# DRAM_DDR4_bank_1_Connector.net
KiCad netlist of a schematic drawn in Altium Designer
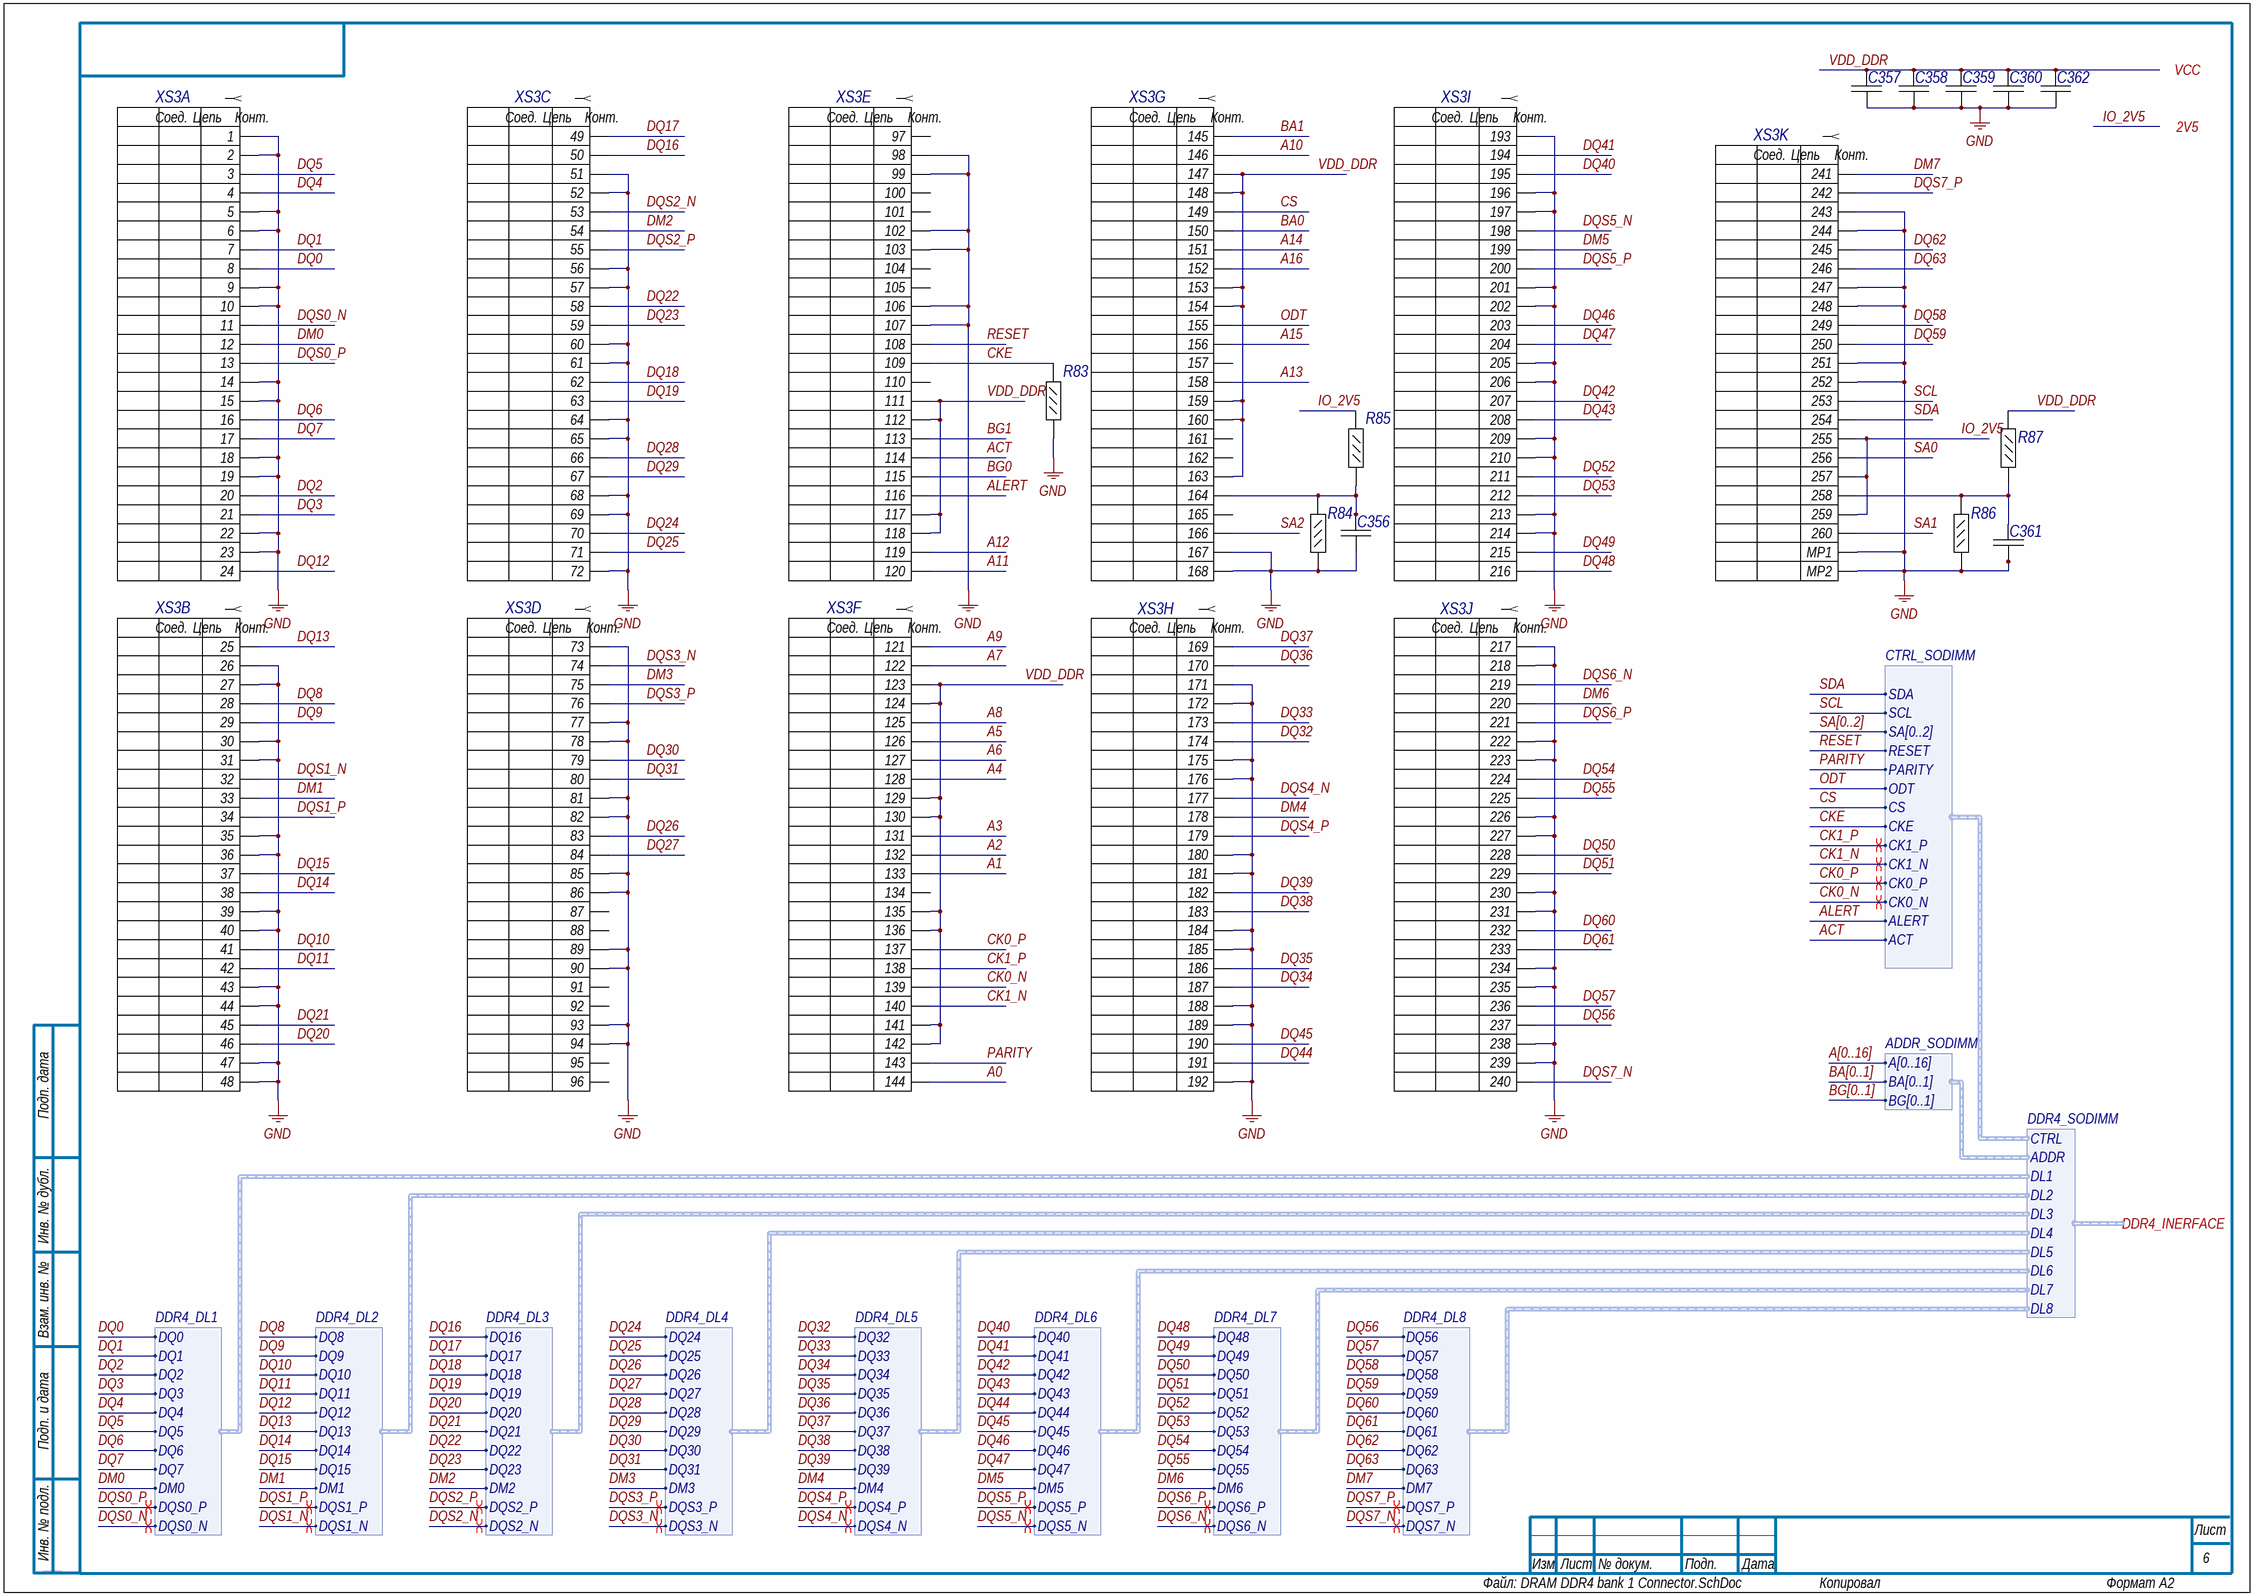
[diagram p0: DRAM DDR4 bank 1 Connector.SchDoc]

(export (version "E")
  (design (tool "Eeschema 10.0.6"))
  (components
    (comp (ref "C356")
      (value "C1005X7R1E104M")
      (footprint "CAPC1005X55X10LL05")
      (description "Chip Capacitor, 0.1 uF, +/- 20%, 25 V, -55 to 125 degC, 0402 (1005 Metric), RoHS, Tape and Reel")
      (fields (field (name "TOLERANCE") "20%"))
      (libsource (lib "MiniPC DB") (part "CAP_NP"))
    )
    (comp (ref "C357")
      (value "C1005X7R1E104M")
      (footprint "CAPC1005X55X10LL05")
      (description "Chip Capacitor, 0.1 uF, +/- 20%, 25 V, -55 to 125 degC, 0402 (1005 Metric), RoHS, Tape and Reel")
      (fields (field (name "TOLERANCE") "20%"))
      (libsource (lib "MiniPC DB") (part "CAP_NP"))
    )
    (comp (ref "C358")
      (value "C1005X7R1E104M")
      (footprint "CAPC1005X55X10LL05")
      (description "Chip Capacitor, 0.1 uF, +/- 20%, 25 V, -55 to 125 degC, 0402 (1005 Metric), RoHS, Tape and Reel")
      (fields (field (name "TOLERANCE") "20%"))
      (libsource (lib "MiniPC DB") (part "CAP_NP"))
    )
    (comp (ref "C359")
      (value "C1005X7R1E104M")
      (footprint "CAPC1005X55X10LL05")
      (description "Chip Capacitor, 0.1 uF, +/- 20%, 25 V, -55 to 125 degC, 0402 (1005 Metric), RoHS, Tape and Reel")
      (fields (field (name "TOLERANCE") "20%"))
      (libsource (lib "MiniPC DB") (part "CAP_NP"))
    )
    (comp (ref "C360")
      (value "C1005X7R1E104M")
      (footprint "CAPC1005X55X10LL05")
      (description "Chip Capacitor, 0.1 uF, +/- 20%, 25 V, -55 to 125 degC, 0402 (1005 Metric), RoHS, Tape and Reel")
      (fields (field (name "TOLERANCE") "20%"))
      (libsource (lib "MiniPC DB") (part "CAP_NP"))
    )
    (comp (ref "C361")
      (value "C1005X7R1E104M")
      (footprint "CAPC1005X55X10LL05")
      (description "Chip Capacitor, 0.1 uF, +/- 20%, 25 V, -55 to 125 degC, 0402 (1005 Metric), RoHS, Tape and Reel")
      (fields (field (name "TOLERANCE") "20%"))
      (libsource (lib "MiniPC DB") (part "CAP_NP"))
    )
    (comp (ref "C362")
      (value "C1005X7R1E104M")
      (footprint "CAPC1005X55X10LL05")
      (description "Chip Capacitor, 0.1 uF, +/- 20%, 25 V, -55 to 125 degC, 0402 (1005 Metric), RoHS, Tape and Reel")
      (fields (field (name "TOLERANCE") "20%"))
      (libsource (lib "MiniPC DB") (part "CAP_NP"))
    )
    (comp (ref "R83")
      (value "RC0402JR-0739RL")
      (footprint "RESC1005X40X25LL05T05")
      (description "Chip Resistor, 39 Ohm, +/- 5%, 0.063 W, -55 to 155 degC, 0402 (1005 Metric), RoHS, Tape and Reel")
      (fields (field (name "TOLERANCE") "5%"))
      (libsource (lib "") (part "RES-0.05_2"))
    )
    (comp (ref "R84")
      (value "RC0402JR-0739RL")
      (footprint "RESC1005X40X25LL05T05")
      (description "Chip Resistor, 39 Ohm, +/- 5%, 0.063 W, -55 to 155 degC, 0402 (1005 Metric), RoHS, Tape and Reel")
      (fields (field (name "TOLERANCE") "5%"))
      (libsource (lib "MiniPC DB") (part "RES-0.05"))
    )
    (comp (ref "R85")
      (value "RC0402JR-0739RL")
      (footprint "RESC1005X40X25LL05T05")
      (description "Chip Resistor, 39 Ohm, +/- 5%, 0.063 W, -55 to 155 degC, 0402 (1005 Metric), RoHS, Tape and Reel")
      (fields (field (name "TOLERANCE") "5%"))
      (libsource (lib "") (part "RES-0.05_1"))
    )
    (comp (ref "R86")
      (value "RC0402JR-0739RL")
      (footprint "RESC1005X40X25LL05T05")
      (description "Chip Resistor, 39 Ohm, +/- 5%, 0.063 W, -55 to 155 degC, 0402 (1005 Metric), RoHS, Tape and Reel")
      (fields (field (name "TOLERANCE") "5%"))
      (libsource (lib "MiniPC DB") (part "RES-0.05"))
    )
    (comp (ref "R87")
      (value "RC0402JR-0739RL")
      (footprint "RESC1005X40X25LL05T05")
      (description "Chip Resistor, 39 Ohm, +/- 5%, 0.063 W, -55 to 155 degC, 0402 (1005 Metric), RoHS, Tape and Reel")
      (fields (field (name "TOLERANCE") "5%"))
      (libsource (lib "") (part "RES-0.05_1"))
    )
    (comp (ref "XS3")
      (value "AS0A823-H8SB-7H")
      (footprint "FOXC-AS0A823-H8SB-7H_V")
      (libsource (lib "MiniPC DB") (part "ROZ_262K"))
    )
  )
  (nets
    (net (code "10") (name "/A0") (class "Default")
      (node (ref "XS3") (pin "144") (pinfunction "144_144") (pintype "passive"))
    )
    (net (code "11") (name "/A1") (class "Default")
      (node (ref "XS3") (pin "133") (pinfunction "133_133") (pintype "passive"))
    )
    (net (code "12") (name "/A2") (class "Default")
      (node (ref "XS3") (pin "132") (pinfunction "132_132") (pintype "passive"))
    )
    (net (code "13") (name "/A3") (class "Default")
      (node (ref "XS3") (pin "131") (pinfunction "131_131") (pintype "passive"))
    )
    (net (code "14") (name "/A4") (class "Default")
      (node (ref "XS3") (pin "128") (pinfunction "128_128") (pintype "passive"))
    )
    (net (code "15") (name "/A5") (class "Default")
      (node (ref "XS3") (pin "126") (pinfunction "126_126") (pintype "passive"))
    )
    (net (code "16") (name "/A6") (class "Default")
      (node (ref "XS3") (pin "127") (pinfunction "127_127") (pintype "passive"))
    )
    (net (code "17") (name "/A7") (class "Default")
      (node (ref "XS3") (pin "122") (pinfunction "122_122") (pintype "passive"))
    )
    (net (code "18") (name "/A8") (class "Default")
      (node (ref "XS3") (pin "125") (pinfunction "125_125") (pintype "passive"))
    )
    (net (code "19") (name "/A9") (class "Default")
      (node (ref "XS3") (pin "121") (pinfunction "121_121") (pintype "passive"))
    )
    (net (code "20") (name "/A10") (class "Default")
      (node (ref "XS3") (pin "146") (pinfunction "146_146") (pintype "passive"))
    )
    (net (code "21") (name "/A11") (class "Default")
      (node (ref "XS3") (pin "120") (pinfunction "120_120") (pintype "passive"))
    )
    (net (code "22") (name "/A12") (class "Default")
      (node (ref "XS3") (pin "119") (pinfunction "119_119") (pintype "passive"))
    )
    (net (code "23") (name "/A13") (class "Default")
      (node (ref "XS3") (pin "158") (pinfunction "158_158") (pintype "passive"))
    )
    (net (code "24") (name "/A14") (class "Default")
      (node (ref "XS3") (pin "151") (pinfunction "151_151") (pintype "passive"))
    )
    (net (code "25") (name "/A15") (class "Default")
      (node (ref "XS3") (pin "156") (pinfunction "156_156") (pintype "passive"))
    )
    (net (code "26") (name "/A16") (class "Default")
      (node (ref "XS3") (pin "152") (pinfunction "152_152") (pintype "passive"))
    )
    (net (code "27") (name "/ACT") (class "Default")
      (node (ref "XS3") (pin "114") (pinfunction "114_114") (pintype "passive"))
    )
    (net (code "28") (name "/ALERT") (class "Default")
      (node (ref "XS3") (pin "116") (pinfunction "116_116") (pintype "passive"))
    )
    (net (code "29") (name "/BA0") (class "Default")
      (node (ref "XS3") (pin "150") (pinfunction "150_150") (pintype "passive"))
    )
    (net (code "30") (name "/BA1") (class "Default")
      (node (ref "XS3") (pin "145") (pinfunction "145_145") (pintype "passive"))
    )
    (net (code "32") (name "/BG0") (class "Default")
      (node (ref "XS3") (pin "115") (pinfunction "115_115") (pintype "passive"))
    )
    (net (code "33") (name "/BG1") (class "Default")
      (node (ref "XS3") (pin "113") (pinfunction "113_113") (pintype "passive"))
    )
    (net (code "35") (name "/CK0_N") (class "Default")
      (node (ref "XS3") (pin "139") (pinfunction "139_139") (pintype "passive"))
    )
    (net (code "36") (name "/CK0_P") (class "Default")
      (node (ref "XS3") (pin "137") (pinfunction "137_137") (pintype "passive"))
    )
    (net (code "37") (name "/CK1_N") (class "Default")
      (node (ref "XS3") (pin "140") (pinfunction "140_140") (pintype "passive"))
    )
    (net (code "38") (name "/CK1_P") (class "Default")
      (node (ref "XS3") (pin "138") (pinfunction "138_138") (pintype "passive"))
    )
    (net (code "39") (name "/CKE") (class "Default")
      (node (ref "R83") (pin "2") (pinfunction "2_2") (pintype "passive"))
      (node (ref "XS3") (pin "109") (pinfunction "109_109") (pintype "passive"))
    )
    (net (code "40") (name "/CS") (class "Default")
      (node (ref "XS3") (pin "149") (pinfunction "149_149") (pintype "passive"))
    )
    (net (code "41") (name "/DM0") (class "Default")
      (node (ref "XS3") (pin "12") (pinfunction "12_12") (pintype "passive"))
    )
    (net (code "42") (name "/DM1") (class "Default")
      (node (ref "XS3") (pin "33") (pinfunction "33_33") (pintype "passive"))
    )
    (net (code "43") (name "/DM2") (class "Default")
      (node (ref "XS3") (pin "54") (pinfunction "54_54") (pintype "passive"))
    )
    (net (code "44") (name "/DM3") (class "Default")
      (node (ref "XS3") (pin "75") (pinfunction "75_75") (pintype "passive"))
    )
    (net (code "45") (name "/DM4") (class "Default")
      (node (ref "XS3") (pin "178") (pinfunction "178_178") (pintype "passive"))
    )
    (net (code "46") (name "/DM5") (class "Default")
      (node (ref "XS3") (pin "199") (pinfunction "199_199") (pintype "passive"))
    )
    (net (code "47") (name "/DM6") (class "Default")
      (node (ref "XS3") (pin "220") (pinfunction "220_220") (pintype "passive"))
    )
    (net (code "48") (name "/DM7") (class "Default")
      (node (ref "XS3") (pin "241") (pinfunction "241_241") (pintype "passive"))
    )
    (net (code "49") (name "/DQ0") (class "Default")
      (node (ref "XS3") (pin "8") (pinfunction "8_8") (pintype "passive"))
    )
    (net (code "50") (name "/DQ1") (class "Default")
      (node (ref "XS3") (pin "7") (pinfunction "7_7") (pintype "passive"))
    )
    (net (code "51") (name "/DQ2") (class "Default")
      (node (ref "XS3") (pin "20") (pinfunction "20_20") (pintype "passive"))
    )
    (net (code "52") (name "/DQ3") (class "Default")
      (node (ref "XS3") (pin "21") (pinfunction "21_21") (pintype "passive"))
    )
    (net (code "53") (name "/DQ4") (class "Default")
      (node (ref "XS3") (pin "4") (pinfunction "4_4") (pintype "passive"))
    )
    (net (code "54") (name "/DQ5") (class "Default")
      (node (ref "XS3") (pin "3") (pinfunction "3_3") (pintype "passive"))
    )
    (net (code "55") (name "/DQ6") (class "Default")
      (node (ref "XS3") (pin "16") (pinfunction "16_16") (pintype "passive"))
    )
    (net (code "56") (name "/DQ7") (class "Default")
      (node (ref "XS3") (pin "17") (pinfunction "17_17") (pintype "passive"))
    )
    (net (code "57") (name "/DQ8") (class "Default")
      (node (ref "XS3") (pin "28") (pinfunction "28_28") (pintype "passive"))
    )
    (net (code "58") (name "/DQ9") (class "Default")
      (node (ref "XS3") (pin "29") (pinfunction "29_29") (pintype "passive"))
    )
    (net (code "59") (name "/DQ10") (class "Default")
      (node (ref "XS3") (pin "41") (pinfunction "41_41") (pintype "passive"))
    )
    (net (code "60") (name "/DQ11") (class "Default")
      (node (ref "XS3") (pin "42") (pinfunction "42_42") (pintype "passive"))
    )
    (net (code "61") (name "/DQ12") (class "Default")
      (node (ref "XS3") (pin "24") (pinfunction "24_24") (pintype "passive"))
    )
    (net (code "62") (name "/DQ13") (class "Default")
      (node (ref "XS3") (pin "25") (pinfunction "25_25") (pintype "passive"))
    )
    (net (code "63") (name "/DQ14") (class "Default")
      (node (ref "XS3") (pin "38") (pinfunction "38_38") (pintype "passive"))
    )
    (net (code "64") (name "/DQ15") (class "Default")
      (node (ref "XS3") (pin "37") (pinfunction "37_37") (pintype "passive"))
    )
    (net (code "65") (name "/DQ16") (class "Default")
      (node (ref "XS3") (pin "50") (pinfunction "50_50") (pintype "passive"))
    )
    (net (code "66") (name "/DQ17") (class "Default")
      (node (ref "XS3") (pin "49") (pinfunction "49_49") (pintype "passive"))
    )
    (net (code "67") (name "/DQ18") (class "Default")
      (node (ref "XS3") (pin "62") (pinfunction "62_62") (pintype "passive"))
    )
    (net (code "68") (name "/DQ19") (class "Default")
      (node (ref "XS3") (pin "63") (pinfunction "63_63") (pintype "passive"))
    )
    (net (code "69") (name "/DQ20") (class "Default")
      (node (ref "XS3") (pin "46") (pinfunction "46_46") (pintype "passive"))
    )
    (net (code "70") (name "/DQ21") (class "Default")
      (node (ref "XS3") (pin "45") (pinfunction "45_45") (pintype "passive"))
    )
    (net (code "71") (name "/DQ22") (class "Default")
      (node (ref "XS3") (pin "58") (pinfunction "58_58") (pintype "passive"))
    )
    (net (code "72") (name "/DQ23") (class "Default")
      (node (ref "XS3") (pin "59") (pinfunction "59_59") (pintype "passive"))
    )
    (net (code "73") (name "/DQ24") (class "Default")
      (node (ref "XS3") (pin "70") (pinfunction "70_70") (pintype "passive"))
    )
    (net (code "74") (name "/DQ25") (class "Default")
      (node (ref "XS3") (pin "71") (pinfunction "71_71") (pintype "passive"))
    )
    (net (code "75") (name "/DQ26") (class "Default")
      (node (ref "XS3") (pin "83") (pinfunction "83_83") (pintype "passive"))
    )
    (net (code "76") (name "/DQ27") (class "Default")
      (node (ref "XS3") (pin "84") (pinfunction "84_84") (pintype "passive"))
    )
    (net (code "77") (name "/DQ28") (class "Default")
      (node (ref "XS3") (pin "66") (pinfunction "66_66") (pintype "passive"))
    )
    (net (code "78") (name "/DQ29") (class "Default")
      (node (ref "XS3") (pin "67") (pinfunction "67_67") (pintype "passive"))
    )
    (net (code "79") (name "/DQ30") (class "Default")
      (node (ref "XS3") (pin "79") (pinfunction "79_79") (pintype "passive"))
    )
    (net (code "80") (name "/DQ31") (class "Default")
      (node (ref "XS3") (pin "80") (pinfunction "80_80") (pintype "passive"))
    )
    (net (code "81") (name "/DQ32") (class "Default")
      (node (ref "XS3") (pin "174") (pinfunction "174_174") (pintype "passive"))
    )
    (net (code "82") (name "/DQ33") (class "Default")
      (node (ref "XS3") (pin "173") (pinfunction "173_173") (pintype "passive"))
    )
    (net (code "83") (name "/DQ34") (class "Default")
      (node (ref "XS3") (pin "187") (pinfunction "187_187") (pintype "passive"))
    )
    (net (code "84") (name "/DQ35") (class "Default")
      (node (ref "XS3") (pin "186") (pinfunction "186_186") (pintype "passive"))
    )
    (net (code "85") (name "/DQ36") (class "Default")
      (node (ref "XS3") (pin "170") (pinfunction "170_170") (pintype "passive"))
    )
    (net (code "86") (name "/DQ37") (class "Default")
      (node (ref "XS3") (pin "169") (pinfunction "169_169") (pintype "passive"))
    )
    (net (code "87") (name "/DQ38") (class "Default")
      (node (ref "XS3") (pin "183") (pinfunction "183_183") (pintype "passive"))
    )
    (net (code "88") (name "/DQ39") (class "Default")
      (node (ref "XS3") (pin "182") (pinfunction "182_182") (pintype "passive"))
    )
    (net (code "89") (name "/DQ40") (class "Default")
      (node (ref "XS3") (pin "195") (pinfunction "195_195") (pintype "passive"))
    )
    (net (code "90") (name "/DQ41") (class "Default")
      (node (ref "XS3") (pin "194") (pinfunction "194_194") (pintype "passive"))
    )
    (net (code "91") (name "/DQ42") (class "Default")
      (node (ref "XS3") (pin "207") (pinfunction "207_207") (pintype "passive"))
    )
    (net (code "92") (name "/DQ43") (class "Default")
      (node (ref "XS3") (pin "208") (pinfunction "208_208") (pintype "passive"))
    )
    (net (code "93") (name "/DQ44") (class "Default")
      (node (ref "XS3") (pin "191") (pinfunction "191_191") (pintype "passive"))
    )
    (net (code "94") (name "/DQ45") (class "Default")
      (node (ref "XS3") (pin "190") (pinfunction "190_190") (pintype "passive"))
    )
    (net (code "95") (name "/DQ46") (class "Default")
      (node (ref "XS3") (pin "203") (pinfunction "203_203") (pintype "passive"))
    )
    (net (code "96") (name "/DQ47") (class "Default")
      (node (ref "XS3") (pin "204") (pinfunction "204_204") (pintype "passive"))
    )
    (net (code "97") (name "/DQ48") (class "Default")
      (node (ref "XS3") (pin "216") (pinfunction "216_216") (pintype "passive"))
    )
    (net (code "98") (name "/DQ49") (class "Default")
      (node (ref "XS3") (pin "215") (pinfunction "215_215") (pintype "passive"))
    )
    (net (code "99") (name "/DQ50") (class "Default")
      (node (ref "XS3") (pin "228") (pinfunction "228_228") (pintype "passive"))
    )
    (net (code "100") (name "/DQ51") (class "Default")
      (node (ref "XS3") (pin "229") (pinfunction "229_229") (pintype "passive"))
    )
    (net (code "101") (name "/DQ52") (class "Default")
      (node (ref "XS3") (pin "211") (pinfunction "211_211") (pintype "passive"))
    )
    (net (code "102") (name "/DQ53") (class "Default")
      (node (ref "XS3") (pin "212") (pinfunction "212_212") (pintype "passive"))
    )
    (net (code "103") (name "/DQ54") (class "Default")
      (node (ref "XS3") (pin "224") (pinfunction "224_224") (pintype "passive"))
    )
    (net (code "104") (name "/DQ55") (class "Default")
      (node (ref "XS3") (pin "225") (pinfunction "225_225") (pintype "passive"))
    )
    (net (code "105") (name "/DQ56") (class "Default")
      (node (ref "XS3") (pin "237") (pinfunction "237_237") (pintype "passive"))
    )
    (net (code "106") (name "/DQ57") (class "Default")
      (node (ref "XS3") (pin "236") (pinfunction "236_236") (pintype "passive"))
    )
    (net (code "107") (name "/DQ58") (class "Default")
      (node (ref "XS3") (pin "249") (pinfunction "249_249") (pintype "passive"))
    )
    (net (code "108") (name "/DQ59") (class "Default")
      (node (ref "XS3") (pin "250") (pinfunction "250_250") (pintype "passive"))
    )
    (net (code "109") (name "/DQ60") (class "Default")
      (node (ref "XS3") (pin "232") (pinfunction "232_232") (pintype "passive"))
    )
    (net (code "110") (name "/DQ61") (class "Default")
      (node (ref "XS3") (pin "233") (pinfunction "233_233") (pintype "passive"))
    )
    (net (code "111") (name "/DQ62") (class "Default")
      (node (ref "XS3") (pin "245") (pinfunction "245_245") (pintype "passive"))
    )
    (net (code "112") (name "/DQ63") (class "Default")
      (node (ref "XS3") (pin "246") (pinfunction "246_246") (pintype "passive"))
    )
    (net (code "113") (name "/DQS0_N") (class "Default")
      (node (ref "XS3") (pin "11") (pinfunction "11_11") (pintype "passive"))
    )
    (net (code "114") (name "/DQS0_P") (class "Default")
      (node (ref "XS3") (pin "13") (pinfunction "13_13") (pintype "passive"))
    )
    (net (code "115") (name "/DQS1_N") (class "Default")
      (node (ref "XS3") (pin "32") (pinfunction "32_32") (pintype "passive"))
    )
    (net (code "116") (name "/DQS1_P") (class "Default")
      (node (ref "XS3") (pin "34") (pinfunction "34_34") (pintype "passive"))
    )
    (net (code "117") (name "/DQS2_N") (class "Default")
      (node (ref "XS3") (pin "53") (pinfunction "53_53") (pintype "passive"))
    )
    (net (code "118") (name "/DQS2_P") (class "Default")
      (node (ref "XS3") (pin "55") (pinfunction "55_55") (pintype "passive"))
    )
    (net (code "119") (name "/DQS3_N") (class "Default")
      (node (ref "XS3") (pin "74") (pinfunction "74_74") (pintype "passive"))
    )
    (net (code "120") (name "/DQS3_P") (class "Default")
      (node (ref "XS3") (pin "76") (pinfunction "76_76") (pintype "passive"))
    )
    (net (code "121") (name "/DQS4_N") (class "Default")
      (node (ref "XS3") (pin "177") (pinfunction "177_177") (pintype "passive"))
    )
    (net (code "122") (name "/DQS4_P") (class "Default")
      (node (ref "XS3") (pin "179") (pinfunction "179_179") (pintype "passive"))
    )
    (net (code "123") (name "/DQS5_N") (class "Default")
      (node (ref "XS3") (pin "198") (pinfunction "198_198") (pintype "passive"))
    )
    (net (code "124") (name "/DQS5_P") (class "Default")
      (node (ref "XS3") (pin "200") (pinfunction "200_200") (pintype "passive"))
    )
    (net (code "125") (name "/DQS6_N") (class "Default")
      (node (ref "XS3") (pin "219") (pinfunction "219_219") (pintype "passive"))
    )
    (net (code "126") (name "/DQS6_P") (class "Default")
      (node (ref "XS3") (pin "221") (pinfunction "221_221") (pintype "passive"))
    )
    (net (code "127") (name "/DQS7_N") (class "Default")
      (node (ref "XS3") (pin "240") (pinfunction "240_240") (pintype "passive"))
    )
    (net (code "128") (name "/DQS7_P") (class "Default")
      (node (ref "XS3") (pin "242") (pinfunction "242_242") (pintype "passive"))
    )
    (net (code "129") (name "/IO_2V5") (class "Default")
      (node (ref "R85") (pin "1") (pinfunction "1_1") (pintype "passive"))
      (node (ref "XS3") (pin "255") (pinfunction "255_255") (pintype "passive"))
      (node (ref "XS3") (pin "257") (pinfunction "257_257") (pintype "passive"))
      (node (ref "XS3") (pin "259") (pinfunction "259_259") (pintype "passive"))
    )
    (net (code "130") (name "/ODT") (class "Default")
      (node (ref "XS3") (pin "155") (pinfunction "155_155") (pintype "passive"))
    )
    (net (code "131") (name "/PARITY") (class "Default")
      (node (ref "XS3") (pin "143") (pinfunction "143_143") (pintype "passive"))
    )
    (net (code "132") (name "/RESET") (class "Default")
      (node (ref "XS3") (pin "108") (pinfunction "108_108") (pintype "passive"))
    )
    (net (code "133") (name "/SA0") (class "Default")
      (node (ref "XS3") (pin "256") (pinfunction "256_256") (pintype "passive"))
    )
    (net (code "134") (name "/SA1") (class "Default")
      (node (ref "XS3") (pin "260") (pinfunction "260_260") (pintype "passive"))
    )
    (net (code "135") (name "/SA2") (class "Default")
      (node (ref "XS3") (pin "166") (pinfunction "166_166") (pintype "passive"))
    )
    (net (code "136") (name "/SCL") (class "Default")
      (node (ref "XS3") (pin "253") (pinfunction "253_253") (pintype "passive"))
    )
    (net (code "137") (name "/SDA") (class "Default")
      (node (ref "XS3") (pin "254") (pinfunction "254_254") (pintype "passive"))
    )
    (net (code "138") (name "/VDD_DDR") (class "Default")
      (node (ref "C357") (pin "1") (pinfunction "1_1") (pintype "passive"))
      (node (ref "C358") (pin "1") (pinfunction "1_1") (pintype "passive"))
      (node (ref "C359") (pin "1") (pinfunction "1_1") (pintype "passive"))
      (node (ref "C360") (pin "1") (pinfunction "1_1") (pintype "passive"))
      (node (ref "C362") (pin "1") (pinfunction "1_1") (pintype "passive"))
      (node (ref "R87") (pin "1") (pinfunction "1_1") (pintype "passive"))
      (node (ref "XS3") (pin "111") (pinfunction "111_111") (pintype "passive"))
      (node (ref "XS3") (pin "112") (pinfunction "112_112") (pintype "passive"))
      (node (ref "XS3") (pin "117") (pinfunction "117_117") (pintype "passive"))
      (node (ref "XS3") (pin "118") (pinfunction "118_118") (pintype "passive"))
      (node (ref "XS3") (pin "123") (pinfunction "123_123") (pintype "passive"))
      (node (ref "XS3") (pin "124") (pinfunction "124_124") (pintype "passive"))
      (node (ref "XS3") (pin "129") (pinfunction "129_129") (pintype "passive"))
      (node (ref "XS3") (pin "130") (pinfunction "130_130") (pintype "passive"))
      (node (ref "XS3") (pin "135") (pinfunction "135_135") (pintype "passive"))
      (node (ref "XS3") (pin "136") (pinfunction "136_136") (pintype "passive"))
      (node (ref "XS3") (pin "141") (pinfunction "141_141") (pintype "passive"))
      (node (ref "XS3") (pin "142") (pinfunction "142_142") (pintype "passive"))
      (node (ref "XS3") (pin "147") (pinfunction "147_147") (pintype "passive"))
      (node (ref "XS3") (pin "148") (pinfunction "148_148") (pintype "passive"))
      (node (ref "XS3") (pin "153") (pinfunction "153_153") (pintype "passive"))
      (node (ref "XS3") (pin "154") (pinfunction "154_154") (pintype "passive"))
      (node (ref "XS3") (pin "159") (pinfunction "159_159") (pintype "passive"))
      (node (ref "XS3") (pin "160") (pinfunction "160_160") (pintype "passive"))
      (node (ref "XS3") (pin "163") (pinfunction "163_163") (pintype "passive"))
    )
    (net (code "150") (name "GND") (class "Default")
      (node (ref "C356") (pin "1") (pinfunction "1_1") (pintype "passive"))
      (node (ref "C357") (pin "2") (pinfunction "2_2") (pintype "passive"))
      (node (ref "C358") (pin "2") (pinfunction "2_2") (pintype "passive"))
      (node (ref "C359") (pin "2") (pinfunction "2_2") (pintype "passive"))
      (node (ref "C360") (pin "2") (pinfunction "2_2") (pintype "passive"))
      (node (ref "C361") (pin "2") (pinfunction "2_2") (pintype "passive"))
      (node (ref "C362") (pin "2") (pinfunction "2_2") (pintype "passive"))
      (node (ref "R83") (pin "1") (pinfunction "1_1") (pintype "passive"))
      (node (ref "R84") (pin "1") (pinfunction "1_1") (pintype "passive"))
      (node (ref "R86") (pin "1") (pinfunction "1_1") (pintype "passive"))
      (node (ref "XS3") (pin "1") (pinfunction "1_1") (pintype "passive"))
      (node (ref "XS3") (pin "10") (pinfunction "10_10") (pintype "passive"))
      (node (ref "XS3") (pin "102") (pinfunction "102_102") (pintype "passive"))
      (node (ref "XS3") (pin "103") (pinfunction "103_103") (pintype "passive"))
      (node (ref "XS3") (pin "106") (pinfunction "106_106") (pintype "passive"))
      (node (ref "XS3") (pin "107") (pinfunction "107_107") (pintype "passive"))
      (node (ref "XS3") (pin "14") (pinfunction "14_14") (pintype "passive"))
      (node (ref "XS3") (pin "15") (pinfunction "15_15") (pintype "passive"))
      (node (ref "XS3") (pin "167") (pinfunction "167_167") (pintype "passive"))
      (node (ref "XS3") (pin "168") (pinfunction "168_168") (pintype "passive"))
      (node (ref "XS3") (pin "171") (pinfunction "171_171") (pintype "passive"))
      (node (ref "XS3") (pin "172") (pinfunction "172_172") (pintype "passive"))
      (node (ref "XS3") (pin "175") (pinfunction "175_175") (pintype "passive"))
      (node (ref "XS3") (pin "176") (pinfunction "176_176") (pintype "passive"))
      (node (ref "XS3") (pin "18") (pinfunction "18_18") (pintype "passive"))
      (node (ref "XS3") (pin "180") (pinfunction "180_180") (pintype "passive"))
      (node (ref "XS3") (pin "181") (pinfunction "181_181") (pintype "passive"))
      (node (ref "XS3") (pin "184") (pinfunction "184_184") (pintype "passive"))
      (node (ref "XS3") (pin "185") (pinfunction "185_185") (pintype "passive"))
      (node (ref "XS3") (pin "188") (pinfunction "188_188") (pintype "passive"))
      (node (ref "XS3") (pin "189") (pinfunction "189_189") (pintype "passive"))
      (node (ref "XS3") (pin "19") (pinfunction "19_19") (pintype "passive"))
      (node (ref "XS3") (pin "192") (pinfunction "192_192") (pintype "passive"))
      (node (ref "XS3") (pin "193") (pinfunction "193_193") (pintype "passive"))
      (node (ref "XS3") (pin "196") (pinfunction "196_196") (pintype "passive"))
      (node (ref "XS3") (pin "197") (pinfunction "197_197") (pintype "passive"))
      (node (ref "XS3") (pin "2") (pinfunction "2_2") (pintype "passive"))
      (node (ref "XS3") (pin "201") (pinfunction "201_201") (pintype "passive"))
      (node (ref "XS3") (pin "202") (pinfunction "202_202") (pintype "passive"))
      (node (ref "XS3") (pin "205") (pinfunction "205_205") (pintype "passive"))
      (node (ref "XS3") (pin "206") (pinfunction "206_206") (pintype "passive"))
      (node (ref "XS3") (pin "209") (pinfunction "209_209") (pintype "passive"))
      (node (ref "XS3") (pin "210") (pinfunction "210_210") (pintype "passive"))
      (node (ref "XS3") (pin "213") (pinfunction "213_213") (pintype "passive"))
      (node (ref "XS3") (pin "214") (pinfunction "214_214") (pintype "passive"))
      (node (ref "XS3") (pin "217") (pinfunction "217_217") (pintype "passive"))
      (node (ref "XS3") (pin "218") (pinfunction "218_218") (pintype "passive"))
      (node (ref "XS3") (pin "22") (pinfunction "22_22") (pintype "passive"))
      (node (ref "XS3") (pin "222") (pinfunction "222_222") (pintype "passive"))
      (node (ref "XS3") (pin "223") (pinfunction "223_223") (pintype "passive"))
      (node (ref "XS3") (pin "226") (pinfunction "226_226") (pintype "passive"))
      (node (ref "XS3") (pin "227") (pinfunction "227_227") (pintype "passive"))
      (node (ref "XS3") (pin "23") (pinfunction "23_23") (pintype "passive"))
      (node (ref "XS3") (pin "230") (pinfunction "230_230") (pintype "passive"))
      (node (ref "XS3") (pin "231") (pinfunction "231_231") (pintype "passive"))
      (node (ref "XS3") (pin "234") (pinfunction "234_234") (pintype "passive"))
      (node (ref "XS3") (pin "235") (pinfunction "235_235") (pintype "passive"))
      (node (ref "XS3") (pin "238") (pinfunction "238_238") (pintype "passive"))
      (node (ref "XS3") (pin "239") (pinfunction "239_239") (pintype "passive"))
      (node (ref "XS3") (pin "243") (pinfunction "243_243") (pintype "passive"))
      (node (ref "XS3") (pin "244") (pinfunction "244_244") (pintype "passive"))
      (node (ref "XS3") (pin "247") (pinfunction "247_247") (pintype "passive"))
      (node (ref "XS3") (pin "248") (pinfunction "248_248") (pintype "passive"))
      (node (ref "XS3") (pin "251") (pinfunction "251_251") (pintype "passive"))
      (node (ref "XS3") (pin "252") (pinfunction "252_252") (pintype "passive"))
      (node (ref "XS3") (pin "26") (pinfunction "26_26") (pintype "passive"))
      (node (ref "XS3") (pin "27") (pinfunction "27_27") (pintype "passive"))
      (node (ref "XS3") (pin "30") (pinfunction "30_30") (pintype "passive"))
      (node (ref "XS3") (pin "31") (pinfunction "31_31") (pintype "passive"))
      (node (ref "XS3") (pin "35") (pinfunction "35_35") (pintype "passive"))
      (node (ref "XS3") (pin "36") (pinfunction "36_36") (pintype "passive"))
      (node (ref "XS3") (pin "39") (pinfunction "39_39") (pintype "passive"))
      (node (ref "XS3") (pin "40") (pinfunction "40_40") (pintype "passive"))
      (node (ref "XS3") (pin "43") (pinfunction "43_43") (pintype "passive"))
      (node (ref "XS3") (pin "44") (pinfunction "44_44") (pintype "passive"))
      (node (ref "XS3") (pin "47") (pinfunction "47_47") (pintype "passive"))
      (node (ref "XS3") (pin "48") (pinfunction "48_48") (pintype "passive"))
      (node (ref "XS3") (pin "5") (pinfunction "5_5") (pintype "passive"))
      (node (ref "XS3") (pin "51") (pinfunction "51_51") (pintype "passive"))
      (node (ref "XS3") (pin "52") (pinfunction "52_52") (pintype "passive"))
      (node (ref "XS3") (pin "56") (pinfunction "56_56") (pintype "passive"))
      (node (ref "XS3") (pin "57") (pinfunction "57_57") (pintype "passive"))
      (node (ref "XS3") (pin "6") (pinfunction "6_6") (pintype "passive"))
      (node (ref "XS3") (pin "60") (pinfunction "60_60") (pintype "passive"))
      (node (ref "XS3") (pin "61") (pinfunction "61_61") (pintype "passive"))
      (node (ref "XS3") (pin "64") (pinfunction "64_64") (pintype "passive"))
      (node (ref "XS3") (pin "65") (pinfunction "65_65") (pintype "passive"))
      (node (ref "XS3") (pin "68") (pinfunction "68_68") (pintype "passive"))
      (node (ref "XS3") (pin "69") (pinfunction "69_69") (pintype "passive"))
      (node (ref "XS3") (pin "72") (pinfunction "72_72") (pintype "passive"))
      (node (ref "XS3") (pin "73") (pinfunction "73_73") (pintype "passive"))
      (node (ref "XS3") (pin "77") (pinfunction "77_77") (pintype "passive"))
      (node (ref "XS3") (pin "78") (pinfunction "78_78") (pintype "passive"))
      (node (ref "XS3") (pin "81") (pinfunction "81_81") (pintype "passive"))
      (node (ref "XS3") (pin "82") (pinfunction "82_82") (pintype "passive"))
      (node (ref "XS3") (pin "85") (pinfunction "85_85") (pintype "passive"))
      (node (ref "XS3") (pin "86") (pinfunction "86_86") (pintype "passive"))
      (node (ref "XS3") (pin "89") (pinfunction "89_89") (pintype "passive"))
      (node (ref "XS3") (pin "9") (pinfunction "9_9") (pintype "passive"))
      (node (ref "XS3") (pin "90") (pinfunction "90_90") (pintype "passive"))
      (node (ref "XS3") (pin "93") (pinfunction "93_93") (pintype "passive"))
      (node (ref "XS3") (pin "94") (pinfunction "94_94") (pintype "passive"))
      (node (ref "XS3") (pin "98") (pinfunction "98_98") (pintype "passive"))
      (node (ref "XS3") (pin "99") (pinfunction "99_99") (pintype "passive"))
      (node (ref "XS3") (pin "MP1") (pinfunction "MP1_MP1") (pintype "passive"))
      (node (ref "XS3") (pin "MP2") (pinfunction "MP2_MP2") (pintype "passive"))
    )
    (net (code "151") (name "Net-(C356-Pad2)") (class "Default")
      (node (ref "C356") (pin "2") (pinfunction "2_2") (pintype "passive"))
      (node (ref "R84") (pin "2") (pinfunction "2_2") (pintype "passive"))
      (node (ref "R85") (pin "2") (pinfunction "2_2") (pintype "passive"))
      (node (ref "XS3") (pin "164") (pinfunction "164_164") (pintype "passive"))
    )
    (net (code "152") (name "Net-(C361-Pad1)") (class "Default")
      (node (ref "C361") (pin "1") (pinfunction "1_1") (pintype "passive"))
      (node (ref "R86") (pin "2") (pinfunction "2_2") (pintype "passive"))
      (node (ref "R87") (pin "2") (pinfunction "2_2") (pintype "passive"))
      (node (ref "XS3") (pin "258") (pinfunction "258_258") (pintype "passive"))
    )
    (net (code "153") (name "unconnected-(XS3-Pad87)") (class "Default")
      (node (ref "XS3") (pin "87") (pinfunction "87_87") (pintype "passive"))
    )
    (net (code "154") (name "unconnected-(XS3-Pad88)") (class "Default")
      (node (ref "XS3") (pin "88") (pinfunction "88_88") (pintype "passive"))
    )
    (net (code "155") (name "unconnected-(XS3-Pad91)") (class "Default")
      (node (ref "XS3") (pin "91") (pinfunction "91_91") (pintype "passive"))
    )
    (net (code "156") (name "unconnected-(XS3-Pad92)") (class "Default")
      (node (ref "XS3") (pin "92") (pinfunction "92_92") (pintype "passive"))
    )
    (net (code "157") (name "unconnected-(XS3-Pad95)") (class "Default")
      (node (ref "XS3") (pin "95") (pinfunction "95_95") (pintype "passive"))
    )
    (net (code "158") (name "unconnected-(XS3-Pad96)") (class "Default")
      (node (ref "XS3") (pin "96") (pinfunction "96_96") (pintype "passive"))
    )
    (net (code "159") (name "unconnected-(XS3-Pad97)") (class "Default")
      (node (ref "XS3") (pin "97") (pinfunction "97_97") (pintype "passive"))
    )
    (net (code "160") (name "unconnected-(XS3-Pad100)") (class "Default")
      (node (ref "XS3") (pin "100") (pinfunction "100_100") (pintype "passive"))
    )
    (net (code "161") (name "unconnected-(XS3-Pad101)") (class "Default")
      (node (ref "XS3") (pin "101") (pinfunction "101_101") (pintype "passive"))
    )
    (net (code "162") (name "unconnected-(XS3-Pad104)") (class "Default")
      (node (ref "XS3") (pin "104") (pinfunction "104_104") (pintype "passive"))
    )
    (net (code "163") (name "unconnected-(XS3-Pad105)") (class "Default")
      (node (ref "XS3") (pin "105") (pinfunction "105_105") (pintype "passive"))
    )
    (net (code "164") (name "unconnected-(XS3-Pad110)") (class "Default")
      (node (ref "XS3") (pin "110") (pinfunction "110_110") (pintype "passive"))
    )
    (net (code "165") (name "unconnected-(XS3-Pad134)") (class "Default")
      (node (ref "XS3") (pin "134") (pinfunction "134_134") (pintype "passive"))
    )
    (net (code "166") (name "unconnected-(XS3-Pad157)") (class "Default")
      (node (ref "XS3") (pin "157") (pinfunction "157_157") (pintype "passive"))
    )
    (net (code "167") (name "unconnected-(XS3-Pad161)") (class "Default")
      (node (ref "XS3") (pin "161") (pinfunction "161_161") (pintype "passive"))
    )
    (net (code "168") (name "unconnected-(XS3-Pad162)") (class "Default")
      (node (ref "XS3") (pin "162") (pinfunction "162_162") (pintype "passive"))
    )
    (net (code "169") (name "unconnected-(XS3-Pad165)") (class "Default")
      (node (ref "XS3") (pin "165") (pinfunction "165_165") (pintype "passive"))
    )
  )
)
